# ADC_PLL.net
KiCad netlist of a schematic drawn in Altium Designer
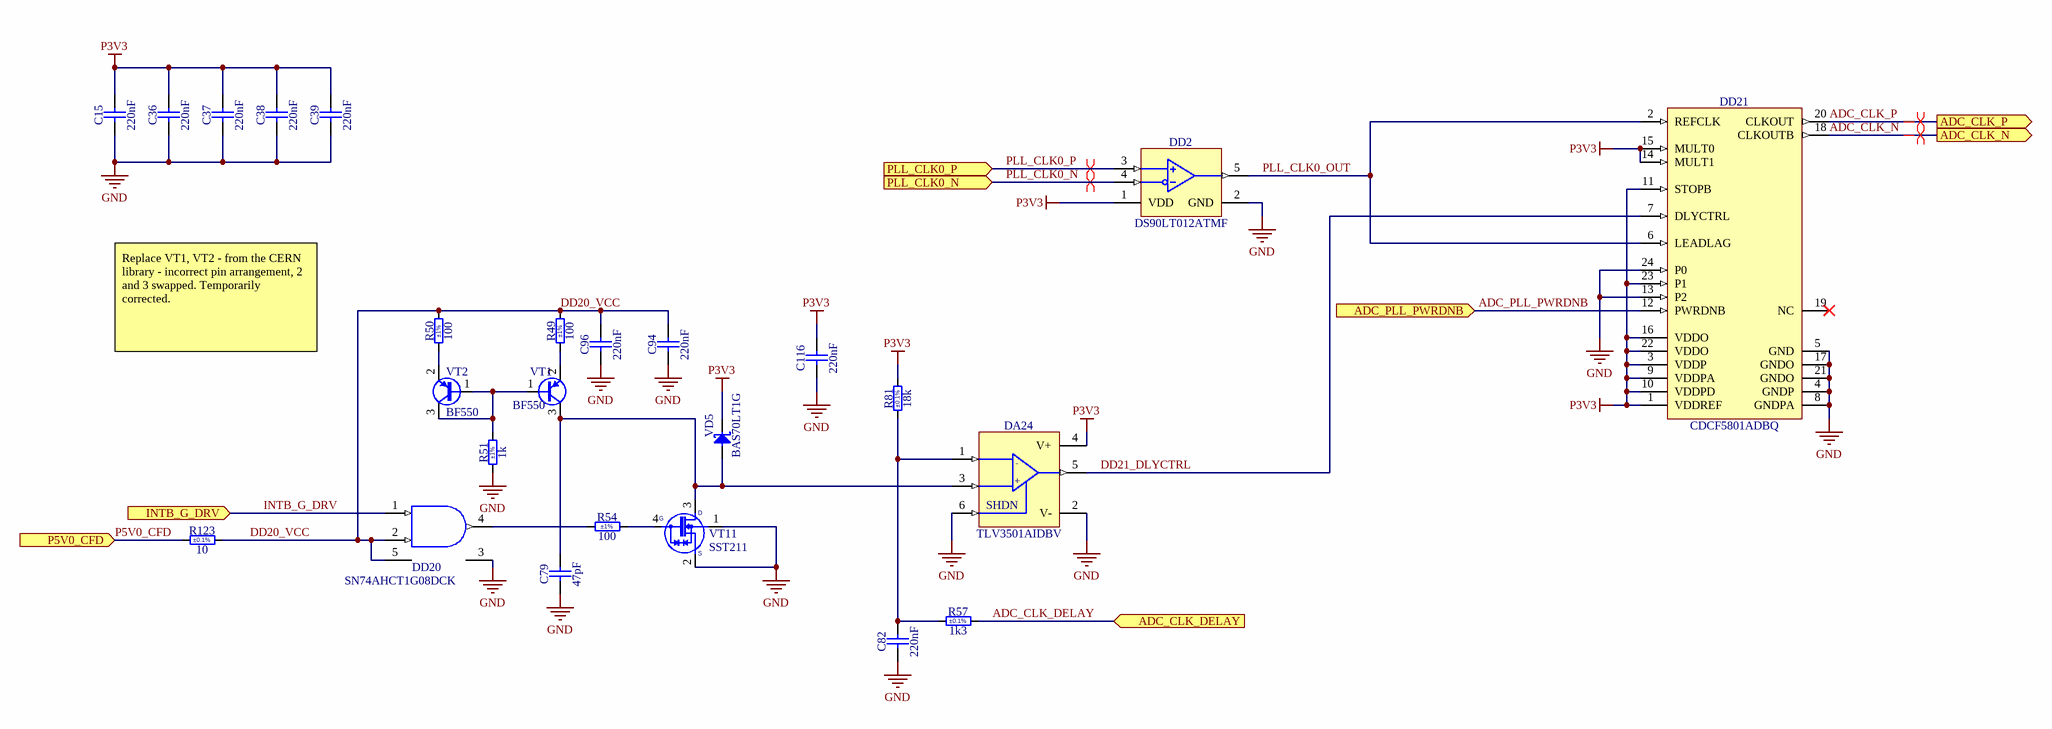
[diagram p0: ADC_PLL.SchDoc]

(export (version "E")
  (design (tool "Eeschema 10.0.6"))
  (components
    (comp (ref "C15")
      (value "220nF")
      (footprint "CAPC1005X55N")
      (description "Non-polarised capacitor")
      (fields
        (field (name "PART NUMBER") "CC0402_220NF_16V_10%_X7R")
        (field (name "VOLTAGE") "16V")
        (field (name "AUTHOR") "CERN DEM JLC")
      )
      (libsource (lib "Capacitors") (part "Capacitor - non polarized"))
    )
    (comp (ref "C36")
      (value "220nF")
      (footprint "CAPC1005X55N")
      (description "Non-polarised capacitor")
      (fields
        (field (name "PART NUMBER") "CC0402_220NF_16V_10%_X7R")
        (field (name "VOLTAGE") "16V")
        (field (name "AUTHOR") "CERN DEM JLC")
      )
      (libsource (lib "Capacitors") (part "Capacitor - non polarized"))
    )
    (comp (ref "C37")
      (value "220nF")
      (footprint "CAPC1005X55N")
      (description "Non-polarised capacitor")
      (fields
        (field (name "PART NUMBER") "CC0402_220NF_16V_10%_X7R")
        (field (name "VOLTAGE") "16V")
        (field (name "AUTHOR") "CERN DEM JLC")
      )
      (libsource (lib "Capacitors") (part "Capacitor - non polarized"))
    )
    (comp (ref "C38")
      (value "220nF")
      (footprint "CAPC1005X55N")
      (description "Non-polarised capacitor")
      (fields
        (field (name "PART NUMBER") "CC0402_220NF_16V_10%_X7R")
        (field (name "VOLTAGE") "16V")
        (field (name "AUTHOR") "CERN DEM JLC")
      )
      (libsource (lib "Capacitors") (part "Capacitor - non polarized"))
    )
    (comp (ref "C39")
      (value "220nF")
      (footprint "CAPC1005X55N")
      (description "Non-polarised capacitor")
      (fields
        (field (name "PART NUMBER") "CC0402_220NF_16V_10%_X7R")
        (field (name "VOLTAGE") "16V")
        (field (name "AUTHOR") "CERN DEM JLC")
      )
      (libsource (lib "Capacitors") (part "Capacitor - non polarized"))
    )
    (comp (ref "C79")
      (value "47pF")
      (footprint "CAPC2012X140N")
      (description "Non-polarised capacitor")
      (fields
        (field (name "PART NUMBER") "CC0805_47pF_50V_2%_X8R")
        (field (name "VOLTAGE") "50V")
        (field (name "AUTHOR") "CERN DEM HF")
      )
      (libsource (lib "Capacitors") (part "Capacitor - non polarized"))
    )
    (comp (ref "C82")
      (value "220nF")
      (footprint "CAPC1005X55N")
      (description "Non-polarised capacitor")
      (fields
        (field (name "PART NUMBER") "CC0402_220NF_16V_10%_X7R")
        (field (name "VOLTAGE") "16V")
        (field (name "AUTHOR") "CERN DEM JLC")
      )
      (libsource (lib "Capacitors") (part "Capacitor - non polarized"))
    )
    (comp (ref "C94")
      (value "220nF")
      (footprint "CAPC1005X55N")
      (description "Non-polarised capacitor")
      (fields
        (field (name "PART NUMBER") "CC0402_220NF_16V_10%_X7R")
        (field (name "VOLTAGE") "16V")
        (field (name "AUTHOR") "CERN DEM JLC")
      )
      (libsource (lib "Capacitors") (part "Capacitor - non polarized"))
    )
    (comp (ref "C96")
      (value "220nF")
      (footprint "CAPC1005X55N")
      (description "Non-polarised capacitor")
      (fields
        (field (name "PART NUMBER") "CC0402_220NF_16V_10%_X7R")
        (field (name "VOLTAGE") "16V")
        (field (name "AUTHOR") "CERN DEM JLC")
      )
      (libsource (lib "Capacitors") (part "Capacitor - non polarized"))
    )
    (comp (ref "C116")
      (value "220nF")
      (footprint "CAPC2012X135N")
      (description "Non-polarised capacitor")
      (fields
        (field (name "PART NUMBER") "CC0805_220NF_50V_10%_X7R")
        (field (name "VOLTAGE") "50V")
        (field (name "AUTHOR") "CERN DEM JLC")
      )
      (libsource (lib "Capacitors") (part "Capacitor - non polarized"))
    )
    (comp (ref "DA24")
      (value "TLV3501AIDBV")
      (footprint "SOT95P280X145-6N")
      (description "Wideband, Fixed Gain, Video Buffer Amplifier With Disable")
      (fields (field (name "MANUFACTURER") "TEXAS INSTRUMENTS") (field (name "AUTHOR") "CERN DEM HF"))
      (libsource (lib "ICs And Semiconductors") (part "TLV3501AIDBV"))
    )
    (comp (ref "DD2")
      (value "DS90LT012ATMF")
      (footprint "SOT95P280X145-5N")
      (description "3V LVDS Single CMOS Differential Line Receiver")
      (fields (field (name "MANUFACTURER") "TEXAS INSTRUMENTS") (field (name "AUTHOR") "CERN DEM HF"))
      (libsource (lib "ICs And Semiconductors") (part "DS90LT012A"))
    )
    (comp (ref "DD20")
      (value "SN74AHCT1G08DCK")
      (footprint "SOT65P210X110-5N")
      (description "Single 2-Input AND Gate")
      (fields (field (name "MANUFACTURER") "TEXAS INSTRUMENTS") (field (name "AUTHOR") "CERN DEM HF"))
      (libsource (lib "ICs And Semiconductors") (part "741G08"))
    )
    (comp (ref "DD21")
      (value "CDCF5801ADBQ")
      (footprint "SOP63P600X175-24N")
      (description "Clock Multiplier with Delay Control and Phase Alignment")
      (fields (field (name "MANUFACTURER") "TEXAS INSTRUMENTS") (field (name "AUTHOR") "CERN DEM HF"))
      (libsource (lib "ICs And Semiconductors") (part "CDCF5801ADBQ"))
    )
    (comp (ref "R49")
      (value "100")
      (footprint "RESC1608X55N")
      (description "Resistor - 1%")
      (fields
        (field (name "TOLERANCE") "±1%")
        (field (name "PART NUMBER") "R0603_100R_1%_0.1W_100PPM")
        (field (name "POWER") "0.1W")
        (field (name "AUTHOR") "CERN DEM JLC")
      )
      (libsource (lib "Resistors") (part "Resistor - 1%"))
    )
    (comp (ref "R50")
      (value "100")
      (footprint "RESC1608X55N")
      (description "Resistor - 1%")
      (fields
        (field (name "TOLERANCE") "±1%")
        (field (name "PART NUMBER") "R0603_100R_1%_0.1W_100PPM")
        (field (name "POWER") "0.1W")
        (field (name "AUTHOR") "CERN DEM JLC")
      )
      (libsource (lib "Resistors") (part "Resistor - 1%"))
    )
    (comp (ref "R51")
      (value "1k")
      (footprint "RESC1005X40N")
      (description "Resistor - 1%")
      (fields
        (field (name "TOLERANCE") "±1%")
        (field (name "PART NUMBER") "R0402_1K_1%_0.0625W_100PPM")
        (field (name "POWER") "0.0625W")
        (field (name "AUTHOR") "CERN DEM JLC")
      )
      (libsource (lib "Resistors") (part "Resistor - 1%"))
    )
    (comp (ref "R54")
      (value "100")
      (footprint "RESC1608X55N")
      (description "Resistor - 1%")
      (fields
        (field (name "TOLERANCE") "±1%")
        (field (name "PART NUMBER") "R0603_100R_1%_0.1W_100PPM")
        (field (name "POWER") "0.1W")
        (field (name "AUTHOR") "CERN DEM JLC")
      )
      (libsource (lib "Resistors") (part "Resistor - 1%"))
    )
    (comp (ref "R57")
      (value "1k3")
      (footprint "RESC2012X60N")
      (description "Resistor - 0.1%")
      (fields
        (field (name "TOLERANCE") "±0.1%")
        (field (name "PART NUMBER") "R0805_1K3_0.1%_0.1W_10PPM")
        (field (name "POWER") "0.1W")
        (field (name "AUTHOR") "CERN DEM JLC")
      )
      (libsource (lib "Resistors") (part "Resistor - 0.1%"))
    )
    (comp (ref "R81")
      (value "18k")
      (footprint "RESC2012X60N")
      (description "Resistor - 0.1%")
      (fields
        (field (name "TOLERANCE") "±0.1%")
        (field (name "PART NUMBER") "R0805_18K_0.1%_0.125W_10PPM")
        (field (name "POWER") "0.125W")
        (field (name "AUTHOR") "CERN DEM HF")
      )
      (libsource (lib "Resistors") (part "Resistor - 0.1%"))
    )
    (comp (ref "R123")
      (value "10")
      (footprint "RESC2012X60N")
      (description "Resistor - 0.1%")
      (fields
        (field (name "TOLERANCE") "±0.1%")
        (field (name "PART NUMBER") "R0805_10R_0.1%_0.1W_10PPM")
        (field (name "POWER") "0.1W")
        (field (name "AUTHOR") "CERN DEM JLC")
      )
      (libsource (lib "Resistors") (part "Resistor - 0.1%"))
    )
    (comp (ref "VD5")
      (value "BAS70LT1G")
      (footprint "SOT95P240X110-3N")
      (description "Diode Schottky  Anode Pin 1 Cathode Pin 3 (Pas de pin 2)")
      (fields
        (field (name "VOLTAGE") "70V")
        (field (name "POWER") "70mA")
        (field (name "AUTHOR") "CERN DEM JLC")
      )
      (libsource (lib "ICs And Semiconductors") (part "Diode Schottky A1C3"))
    )
    (comp (ref "VT1")
      (value "BF550")
      (footprint "SOT95P230X110-3N")
      (description "PNP Transistor")
      (fields (field (name "MANUFACTURER") "NXP SEMICONDUCTORS") (field (name "AUTHOR") "CERN DEM HF"))
      (libsource (lib "ICs And Semiconductors") (part "PNP B1 C2 E3"))
    )
    (comp (ref "VT2")
      (value "BF550")
      (footprint "SOT95P230X110-3N")
      (description "PNP Transistor")
      (fields (field (name "MANUFACTURER") "NXP SEMICONDUCTORS") (field (name "AUTHOR") "CERN DEM HF"))
      (libsource (lib "ICs And Semiconductors") (part "PNP B1 C2 E3"))
    )
    (comp (ref "VT11")
      (value "SST211")
      (footprint "SOT143N")
      (description "30V, 50 mA N-Channel Enhancement Switching Transistor")
      (fields (field (name "MANUFACTURER") "Linear Systems") (field (name "AUTHOR") "CERN DEM JLC"))
      (libsource (lib "templib") (part "SST211"))
    )
  )
  (nets
    (net (code "1") (name "/ADC_CLK_DELAY") (class "Default")
      (node (ref "R57") (pin "2") (pinfunction "2_2") (pintype "passive"))
    )
    (net (code "2") (name "/ADC_CLK_N") (class "Default")
      (node (ref "DD21") (pin "18") (pinfunction "CLKOUTB_18") (pintype "output"))
    )
    (net (code "3") (name "/ADC_CLK_P") (class "Default")
      (node (ref "DD21") (pin "20") (pinfunction "CLKOUT_20") (pintype "output"))
    )
    (net (code "4") (name "/ADC_PLL_PWRDNB") (class "Default")
      (node (ref "DD21") (pin "12") (pinfunction "PWRDNB_12") (pintype "input"))
    )
    (net (code "5") (name "/DD20_VCC") (class "Default")
      (node (ref "C94") (pin "2") (pinfunction "2_2") (pintype "passive"))
      (node (ref "C96") (pin "2") (pinfunction "2_2") (pintype "passive"))
      (node (ref "DD20") (pin "2") (pinfunction "A_2") (pintype "input"))
      (node (ref "DD20") (pin "5") (pinfunction "VCC_5") (pintype "power_in"))
      (node (ref "R123") (pin "2") (pinfunction "2_2") (pintype "passive"))
      (node (ref "R49") (pin "2") (pinfunction "2_2") (pintype "passive"))
      (node (ref "R50") (pin "2") (pinfunction "2_2") (pintype "passive"))
    )
    (net (code "6") (name "/DD21_DLYCTRL") (class "Default")
      (node (ref "DA24") (pin "5") (pinfunction "OUT_5") (pintype "output"))
      (node (ref "DD21") (pin "7") (pinfunction "DLYCTRL_7") (pintype "input"))
    )
    (net (code "7") (name "/INTB_G_DRV") (class "Default")
      (node (ref "DD20") (pin "1") (pinfunction "B_1") (pintype "input"))
    )
    (net (code "8") (name "/P5V0_CFD") (class "Default")
      (node (ref "R123") (pin "1") (pinfunction "1_1") (pintype "passive"))
    )
    (net (code "9") (name "/PLL_CLK0_N") (class "Default")
      (node (ref "DD2") (pin "4") (pinfunction "IN-_4") (pintype "input"))
    )
    (net (code "10") (name "/PLL_CLK0_OUT") (class "Default")
      (node (ref "DD2") (pin "5") (pinfunction "TTLOUT_5") (pintype "output"))
      (node (ref "DD21") (pin "2") (pinfunction "REFCLK_2") (pintype "input"))
      (node (ref "DD21") (pin "6") (pinfunction "LEADLAG_6") (pintype "input"))
    )
    (net (code "11") (name "/PLL_CLK0_P") (class "Default")
      (node (ref "DD2") (pin "3") (pinfunction "IN+_3") (pintype "input"))
    )
    (net (code "12") (name "GND") (class "Default")
      (node (ref "C116") (pin "1") (pinfunction "1_1") (pintype "passive"))
      (node (ref "C15") (pin "1") (pinfunction "1_1") (pintype "passive"))
      (node (ref "C36") (pin "1") (pinfunction "1_1") (pintype "passive"))
      (node (ref "C37") (pin "1") (pinfunction "1_1") (pintype "passive"))
      (node (ref "C38") (pin "1") (pinfunction "1_1") (pintype "passive"))
      (node (ref "C39") (pin "1") (pinfunction "1_1") (pintype "passive"))
      (node (ref "C79") (pin "1") (pinfunction "1_1") (pintype "passive"))
      (node (ref "C82") (pin "1") (pinfunction "1_1") (pintype "passive"))
      (node (ref "C94") (pin "1") (pinfunction "1_1") (pintype "passive"))
      (node (ref "C96") (pin "1") (pinfunction "1_1") (pintype "passive"))
      (node (ref "DA24") (pin "2") (pinfunction "V-_2") (pintype "power_in"))
      (node (ref "DA24") (pin "6") (pinfunction "SHDN_6") (pintype "input"))
      (node (ref "DD2") (pin "2") (pinfunction "GND_2") (pintype "power_in"))
      (node (ref "DD20") (pin "3") (pinfunction "GND_3") (pintype "power_in"))
      (node (ref "DD21") (pin "13") (pinfunction "P2_13") (pintype "input"))
      (node (ref "DD21") (pin "17") (pinfunction "GNDO_17") (pintype "power_in"))
      (node (ref "DD21") (pin "21") (pinfunction "GNDO_21") (pintype "power_in"))
      (node (ref "DD21") (pin "24") (pinfunction "P0_24") (pintype "input"))
      (node (ref "DD21") (pin "4") (pinfunction "GNDP_4") (pintype "power_in"))
      (node (ref "DD21") (pin "5") (pinfunction "GND_5") (pintype "power_in"))
      (node (ref "DD21") (pin "8") (pinfunction "GNDPA_8") (pintype "power_in"))
      (node (ref "R51") (pin "1") (pinfunction "1_1") (pintype "passive"))
      (node (ref "VT11") (pin "1") (pinfunction "SUB_1") (pintype "passive"))
      (node (ref "VT11") (pin "2") (pinfunction "S_2") (pintype "passive"))
    )
    (net (code "13") (name "Net-(DA24-+IN)") (class "Default")
      (node (ref "C79") (pin "2") (pinfunction "2_2") (pintype "passive"))
      (node (ref "DA24") (pin "3") (pinfunction "+IN_3") (pintype "input"))
      (node (ref "VD5") (pin "1") (pinfunction "A_1") (pintype "passive"))
      (node (ref "VT1") (pin "3") (pinfunction "E_3") (pintype "passive"))
      (node (ref "VT11") (pin "3") (pinfunction "D_3") (pintype "passive"))
    )
    (net (code "14") (name "Net-(DA24--IN)") (class "Default")
      (node (ref "C82") (pin "2") (pinfunction "2_2") (pintype "passive"))
      (node (ref "DA24") (pin "1") (pinfunction "-IN_1") (pintype "input"))
      (node (ref "R57") (pin "1") (pinfunction "1_1") (pintype "passive"))
      (node (ref "R81") (pin "1") (pinfunction "1_1") (pintype "passive"))
    )
    (net (code "15") (name "Net-(DD20-Y)") (class "Default")
      (node (ref "DD20") (pin "4") (pinfunction "Y_4") (pintype "output"))
      (node (ref "R54") (pin "1") (pinfunction "1_1") (pintype "passive"))
    )
    (net (code "16") (name "Net-(VT1-B)") (class "Default")
      (node (ref "R51") (pin "2") (pinfunction "2_2") (pintype "passive"))
      (node (ref "VT1") (pin "1") (pinfunction "B_1") (pintype "passive"))
      (node (ref "VT2") (pin "1") (pinfunction "B_1") (pintype "passive"))
      (node (ref "VT2") (pin "3") (pinfunction "E_3") (pintype "passive"))
    )
    (net (code "17") (name "Net-(VT1-C)") (class "Default")
      (node (ref "R49") (pin "1") (pinfunction "1_1") (pintype "passive"))
      (node (ref "VT1") (pin "2") (pinfunction "C_2") (pintype "passive"))
    )
    (net (code "18") (name "Net-(VT2-C)") (class "Default")
      (node (ref "R50") (pin "1") (pinfunction "1_1") (pintype "passive"))
      (node (ref "VT2") (pin "2") (pinfunction "C_2") (pintype "passive"))
    )
    (net (code "19") (name "Net-(VT11-G)") (class "Default")
      (node (ref "R54") (pin "2") (pinfunction "2_2") (pintype "passive"))
      (node (ref "VT11") (pin "4") (pinfunction "G_4") (pintype "passive"))
    )
    (net (code "20") (name "P3V3") (class "Default")
      (node (ref "C116") (pin "2") (pinfunction "2_2") (pintype "passive"))
      (node (ref "C15") (pin "2") (pinfunction "2_2") (pintype "passive"))
      (node (ref "C36") (pin "2") (pinfunction "2_2") (pintype "passive"))
      (node (ref "C37") (pin "2") (pinfunction "2_2") (pintype "passive"))
      (node (ref "C38") (pin "2") (pinfunction "2_2") (pintype "passive"))
      (node (ref "C39") (pin "2") (pinfunction "2_2") (pintype "passive"))
      (node (ref "DA24") (pin "4") (pinfunction "V+_4") (pintype "power_in"))
      (node (ref "DD2") (pin "1") (pinfunction "VDD_1") (pintype "power_in"))
      (node (ref "DD21") (pin "1") (pinfunction "VDDREF_1") (pintype "power_in"))
      (node (ref "DD21") (pin "10") (pinfunction "VDDPD_10") (pintype "power_in"))
      (node (ref "DD21") (pin "11") (pinfunction "STOPB_11") (pintype "input"))
      (node (ref "DD21") (pin "14") (pinfunction "MULT1_14") (pintype "input"))
      (node (ref "DD21") (pin "15") (pinfunction "MULT0_15") (pintype "input"))
      (node (ref "DD21") (pin "16") (pinfunction "VDDO_16") (pintype "power_in"))
      (node (ref "DD21") (pin "22") (pinfunction "VDDO_22") (pintype "power_in"))
      (node (ref "DD21") (pin "23") (pinfunction "P1_23") (pintype "input"))
      (node (ref "DD21") (pin "3") (pinfunction "VDDP_3") (pintype "power_in"))
      (node (ref "DD21") (pin "9") (pinfunction "VDDPA_9") (pintype "power_in"))
      (node (ref "R81") (pin "2") (pinfunction "2_2") (pintype "passive"))
      (node (ref "VD5") (pin "3") (pinfunction "C_3") (pintype "passive"))
    )
    (net (code "21") (name "unconnected-(DD21-NC-Pad19)") (class "Default")
      (node (ref "DD21") (pin "19") (pinfunction "NC_19") (pintype "passive+no_connect"))
    )
  )
)
